# TAJ1051T.net
KiCad netlist of a schematic drawn in Altium Designer
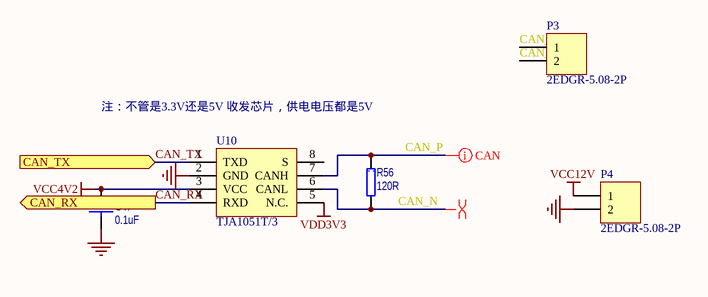
[diagram p0: TAJ1051T.SchDoc]

(export (version "E")
  (design (tool "Eeschema 10.0.6"))
  (components
    (comp (ref "C47")
      (value "0.1uF")
      (footprint "2012[0805]06CD")
      (description "Capacitor")
      (fields (field (name "MANUFACTURER") "TDK"))
      (libsource (lib "*") (part "CAP"))
    )
    (comp (ref "P3")
      (value "2EDGR-5.08-2P")
      (footprint "2EDGR-5.08-2P")
      (description "Header, 2-Pin")
      (fields (field (name "PUBLISHER") "Altium Limited"))
      (libsource (lib "Miscellaneous Connectors") (part "Header 2"))
    )
    (comp (ref "P4")
      (value "2EDGR-5.08-2P")
      (footprint "2EDGR-5.08-2P")
      (description "Header, 2-Pin")
      (fields (field (name "PUBLISHER") "Altium Limited"))
      (libsource (lib "Miscellaneous Connectors") (part "Header 2"))
    )
    (comp (ref "R56")
      (value "120R")
      (footprint "2012[0805]R")
      (description "RES")
      (fields (field (name "MANUFACTURER") "vishay"))
      (libsource (lib "*") (part "RES"))
    )
    (comp (ref "U10")
      (value "TJA1051T/3")
      (footprint "SOIC8_N")
      (description "IC")
      (libsource (lib "S3C2440V9") (part "TJA1051T/3"))
    )
  )
  (nets
    (net (code "1") (name "/CAN_N") (class "Default")
      (node (ref "P3") (pin "2") (pinfunction "2_2") (pintype "passive"))
      (node (ref "R56") (pin "2") (pinfunction "2_2") (pintype "passive"))
      (node (ref "U10") (pin "6") (pinfunction "CANL_6") (pintype "passive"))
    )
    (net (code "2") (name "/CAN_P") (class "Default")
      (node (ref "P3") (pin "1") (pinfunction "1_1") (pintype "passive"))
      (node (ref "R56") (pin "1") (pinfunction "1_1") (pintype "passive"))
      (node (ref "U10") (pin "7") (pinfunction "CANH_7") (pintype "passive"))
    )
    (net (code "3") (name "/CAN_RX") (class "Default")
      (node (ref "U10") (pin "4") (pinfunction "RXD_4") (pintype "passive"))
    )
    (net (code "4") (name "/CAN_TX") (class "Default")
      (node (ref "U10") (pin "1") (pinfunction "TXD_1") (pintype "passive"))
    )
    (net (code "5") (name "GND") (class "Default")
      (node (ref "C47") (pin "2") (pinfunction "2_2") (pintype "passive"))
      (node (ref "P4") (pin "2") (pinfunction "2_2") (pintype "passive"))
      (node (ref "U10") (pin "2") (pinfunction "GND_2") (pintype "passive"))
    )
    (net (code "6") (name "VCC4V2") (class "Default")
      (node (ref "C47") (pin "1") (pinfunction "1_1") (pintype "passive"))
      (node (ref "U10") (pin "3") (pinfunction "VCC_3") (pintype "passive"))
    )
    (net (code "7") (name "VCC12V") (class "Default")
      (node (ref "P4") (pin "1") (pinfunction "1_1") (pintype "passive"))
    )
    (net (code "8") (name "VDD3V3") (class "Default")
      (node (ref "U10") (pin "5") (pinfunction "N.C._5") (pintype "passive"))
    )
    (net (code "9") (name "unconnected-(U10-S-Pad8)") (class "Default")
      (node (ref "U10") (pin "8") (pinfunction "S_8") (pintype "passive"))
    )
  )
)
